# 2-18_11_03_04_08_3.net
KiCad netlist of a schematic drawn in Altium Designer
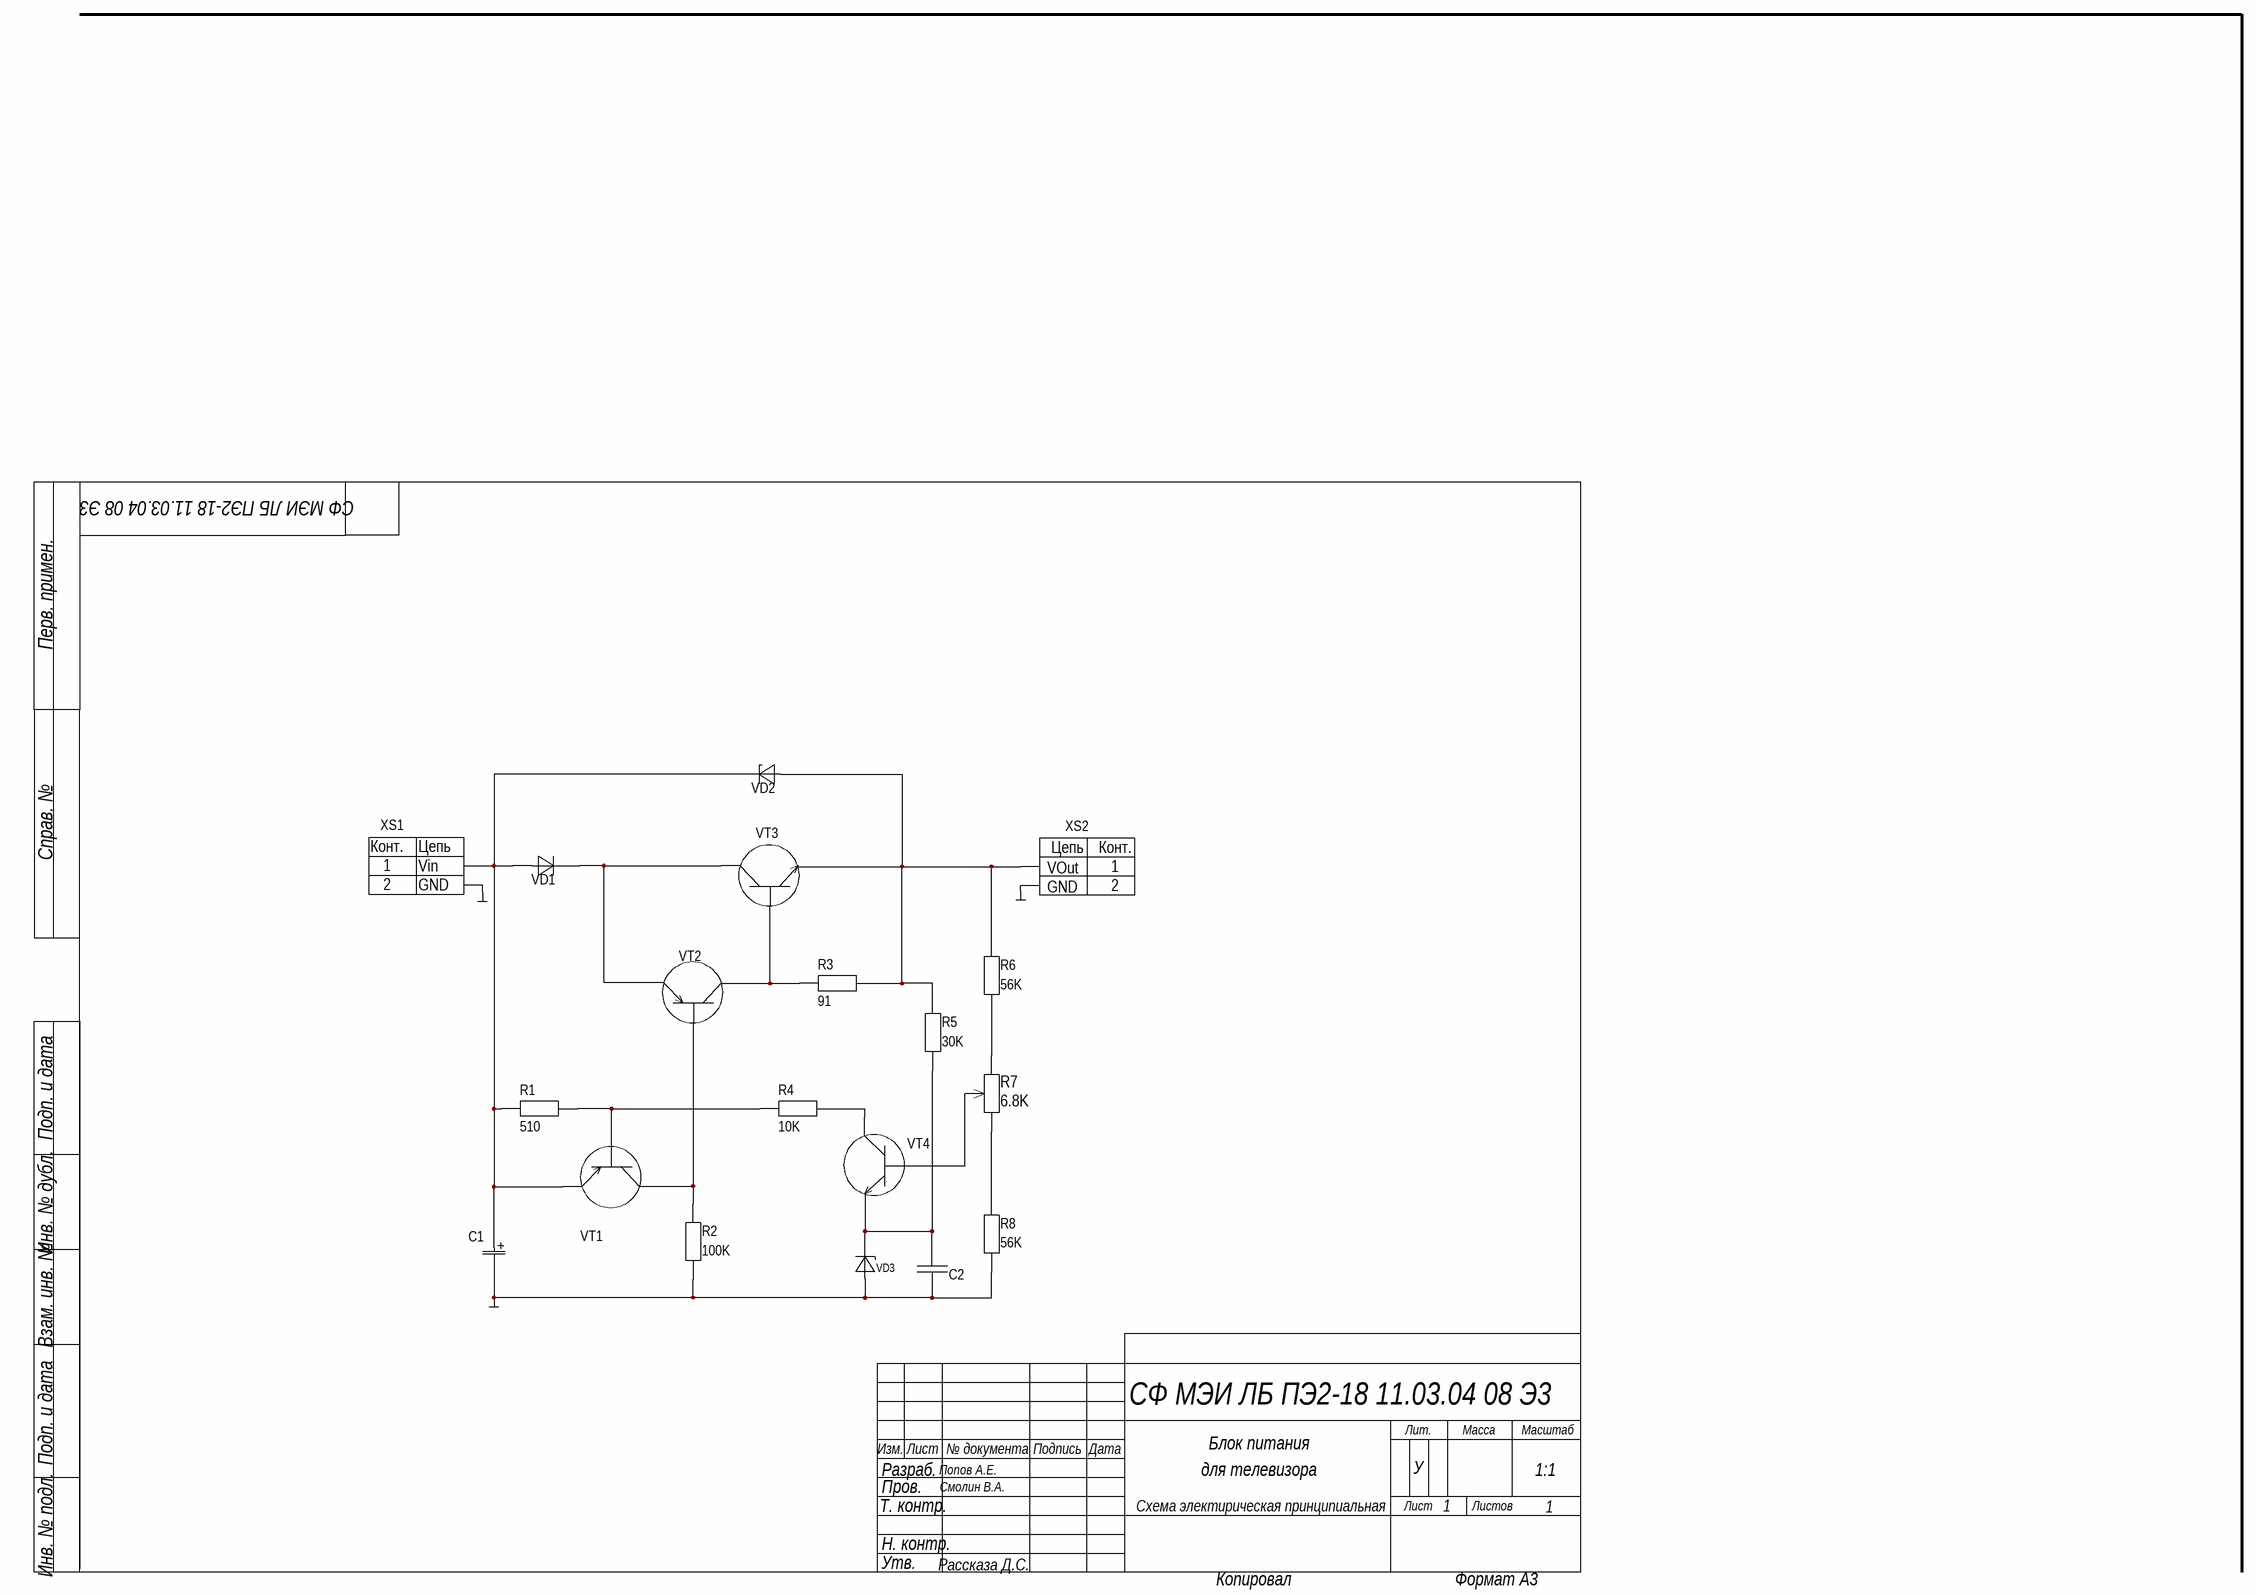
[diagram p0: СФ МЭИ ЛБ ПЭ2-18 11.03.04 08 Э3.SchDoc]

(export (version "E")
  (design (tool "Eeschema 10.0.6"))
  (components
    (comp (ref "C1")
      (value "Part Number: 35TZV330M10X10.5")
      (footprint "CAP_J-V_10X10P5")
      (description "No Description Available")
      (fields
        (field (name "MANUFACTURER_PART_NUMBER") "35TZV330M10X10.5")
        (field (name "COPYRIGHT") "Copyright (C) 2018 Accelerated Designs. All rights reserved")
      )
      (libsource (lib "SMD Elektrilits") (part "35TZV330M10X10.5"))
    )
    (comp (ref "C2")
      (value "0.068u")
      (footprint "0805")
      (description "К53-68\"R\"-25В-0.068 мкФ ±10%")
      (libsource (lib "УГО") (part "К53-68{dblquote}R{dblquote}-25В-0.068 мкФ ±10% 0805"))
    )
    (comp (ref "R1")
      (value "510")
      (footprint "0805")
      (description "0805-0.125 Вт -300 Ом±5%")
      (libsource (lib "УГО") (part "0.125Вт 0805 300 Ом, 5%, Чип резистор (SMD)"))
    )
    (comp (ref "R2")
      (value "100K")
      (footprint "0805")
      (description "0805-0.125 Вт -300 Ом±5%")
      (libsource (lib "УГО") (part "0.125Вт 0805 300 Ом, 5%, Чип резистор (SMD)"))
    )
    (comp (ref "R3")
      (value "91")
      (footprint "0805")
      (description "0805-0.125 Вт -300 Ом±5%")
      (libsource (lib "УГО") (part "0.125Вт 0805 300 Ом, 5%, Чип резистор (SMD)"))
    )
    (comp (ref "R4")
      (value "10K")
      (footprint "0805")
      (description "0805-0.125 Вт -300 Ом±5%")
      (libsource (lib "УГО") (part "0.125Вт 0805 300 Ом, 5%, Чип резистор (SMD)"))
    )
    (comp (ref "R5")
      (value "30K")
      (footprint "0805")
      (description "0805-0.125 Вт -300 Ом±5%")
      (libsource (lib "УГО") (part "0.125Вт 0805 300 Ом, 5%, Чип резистор (SMD)"))
    )
    (comp (ref "R6")
      (value "56K")
      (footprint "0805")
      (description "0805-0.125 Вт -300 Ом±5%")
      (libsource (lib "УГО") (part "0.125Вт 0805 300 Ом, 5%, Чип резистор (SMD)"))
    )
    (comp (ref "R7")
      (value "6.8K")
      (footprint "ST32")
      (description "0805-0.125 Вт -6.8 кОм±5%")
      (libsource (lib "УГО") (part "0.125Вт 0805 6.8 кОм, 5%, подстроечный чип резистор (SMD)"))
    )
    (comp (ref "R8")
      (value "56K")
      (footprint "0805")
      (description "0805-0.125 Вт -300 Ом±5%")
      (libsource (lib "УГО") (part "0.125Вт 0805 300 Ом, 5%, Чип резистор (SMD)"))
    )
    (comp (ref "VD1")
      (value "MMSZ5235B_1")
      (footprint "SOD-123")
      (description "MMSZ5235B")
      (libsource (lib "УГО") (part "MMSZ5235B_1"))
    )
    (comp (ref "VD2") (value "MMSZ5235B") (footprint "SOD-123") (libsource (lib "УГО") (part "MMSZ5235B")))
    (comp (ref "VD3") (value "MMSZ5235B") (footprint "SOD-123") (libsource (lib "УГО") (part "MMSZ5235B")))
    (comp (ref "VT1")
      (value "Биполярный транзистор n-p-n")
      (footprint "SOT23")
      (description "IRFML8244TRPBF")
      (libsource (lib "УГО") (part "IRFML8244TRPBF_1"))
    )
    (comp (ref "VT2")
      (value "Биполярный транзистор n-p-n")
      (footprint "SOT23")
      (description "IRFML8244TRPBF")
      (libsource (lib "УГО") (part "IRFML8244TRPBF_1"))
    )
    (comp (ref "VT3")
      (value "Биполярный транзистор n-p-n")
      (footprint "SOT23")
      (description "IRFML8244TRPBF")
      (libsource (lib "УГО") (part "IRFML8244TRPBF"))
    )
    (comp (ref "VT4")
      (value "Биполярный транзистор n-p-n")
      (footprint "SOT23")
      (description "IRFML8244TRPBF")
      (libsource (lib "УГО") (part "IRFML8244TRPBF"))
    )
    (comp (ref "XS1")
      (value "DG126-5.0-0.2P")
      (footprint "DG126-5.0-02P")
      (libsource (lib "УГО") (part "DG126-5.0-0.2P"))
    )
    (comp (ref "XS2")
      (value "DG126-5.0-0.2P")
      (footprint "DG126-5.0-02P")
      (libsource (lib "УГО") (part "DG126-5.0-0.2P"))
    )
  )
  (nets
    (net (code "1") (name "<NO NET>") (class "Default")
      (node (ref "C1") (pin "2") (pinfunction "2_2") (pintype "power_in"))
      (node (ref "C2") (pin "1") (pinfunction "1_1") (pintype "passive"))
      (node (ref "R2") (pin "1") (pinfunction "1_1") (pintype "passive"))
      (node (ref "R8") (pin "1") (pinfunction "1_1") (pintype "passive"))
      (node (ref "VD3") (pin "1") (pinfunction "In_1") (pintype "passive"))
      (node (ref "XS1") (pin "2") (pinfunction "Pin2_2") (pintype "passive"))
      (node (ref "XS2") (pin "2") (pinfunction "Pin2_2") (pintype "passive"))
    )
    (net (code "2") (name "Net-(R6-Pad1)") (class "Default")
      (node (ref "R6") (pin "1") (pinfunction "1_1") (pintype "passive"))
      (node (ref "R7") (pin "2") (pinfunction "2_2") (pintype "passive"))
    )
    (net (code "3") (name "Net-(R7-Pad1)") (class "Default")
      (node (ref "R7") (pin "1") (pinfunction "1_1") (pintype "passive"))
      (node (ref "R8") (pin "2") (pinfunction "2_2") (pintype "passive"))
    )
    (net (code "4") (name "Net-(VD1-In)") (class "Default")
      (node (ref "C1") (pin "1") (pinfunction "1_1") (pintype "power_in"))
      (node (ref "R1") (pin "1") (pinfunction "1_1") (pintype "passive"))
      (node (ref "VD1") (pin "1") (pinfunction "In_1") (pintype "passive"))
      (node (ref "VD2") (pin "2") (pinfunction "Out_2") (pintype "passive"))
      (node (ref "VT1") (pin "2") (pinfunction "E_2") (pintype "passive"))
      (node (ref "XS1") (pin "1") (pinfunction "Pin1_1") (pintype "passive"))
    )
    (net (code "5") (name "Net-(VD1-Out)") (class "Default")
      (node (ref "VD1") (pin "2") (pinfunction "Out_2") (pintype "passive"))
      (node (ref "VT2") (pin "2") (pinfunction "E_2") (pintype "passive"))
      (node (ref "VT3") (pin "2") (pinfunction "E_2") (pintype "passive"))
    )
    (net (code "6") (name "Net-(VD2-In)") (class "Default")
      (node (ref "R3") (pin "2") (pinfunction "2_2") (pintype "passive"))
      (node (ref "R5") (pin "2") (pinfunction "2_2") (pintype "passive"))
      (node (ref "R6") (pin "2") (pinfunction "2_2") (pintype "passive"))
      (node (ref "VD2") (pin "1") (pinfunction "In_1") (pintype "passive"))
      (node (ref "VT3") (pin "3") (pinfunction "K_3") (pintype "passive"))
      (node (ref "XS2") (pin "1") (pinfunction "Pin1_1") (pintype "passive"))
    )
    (net (code "7") (name "Net-(VD3-Out)") (class "Default")
      (node (ref "C2") (pin "2") (pinfunction "2_2") (pintype "passive"))
      (node (ref "R5") (pin "1") (pinfunction "1_1") (pintype "passive"))
      (node (ref "VD3") (pin "2") (pinfunction "Out_2") (pintype "passive"))
      (node (ref "VT4") (pin "3") (pinfunction "K_3") (pintype "passive"))
    )
    (net (code "8") (name "Net-(VT1-B)") (class "Default")
      (node (ref "R1") (pin "2") (pinfunction "2_2") (pintype "passive"))
      (node (ref "R4") (pin "1") (pinfunction "1_1") (pintype "passive"))
      (node (ref "VT1") (pin "1") (pinfunction "B_1") (pintype "passive"))
    )
    (net (code "9") (name "Net-(VT1-K)") (class "Default")
      (node (ref "R2") (pin "2") (pinfunction "2_2") (pintype "passive"))
      (node (ref "VT1") (pin "3") (pinfunction "K_3") (pintype "passive"))
      (node (ref "VT2") (pin "1") (pinfunction "B_1") (pintype "passive"))
    )
    (net (code "10") (name "Net-(VT2-K)") (class "Default")
      (node (ref "R3") (pin "1") (pinfunction "1_1") (pintype "passive"))
      (node (ref "VT2") (pin "3") (pinfunction "K_3") (pintype "passive"))
      (node (ref "VT3") (pin "1") (pinfunction "B_1") (pintype "passive"))
    )
    (net (code "11") (name "Net-(VT4-B)") (class "Default")
      (node (ref "R7") (pin "3") (pinfunction "3_3") (pintype "passive"))
      (node (ref "VT4") (pin "1") (pinfunction "B_1") (pintype "passive"))
    )
    (net (code "12") (name "Net-(VT4-E)") (class "Default")
      (node (ref "R4") (pin "2") (pinfunction "2_2") (pintype "passive"))
      (node (ref "VT4") (pin "2") (pinfunction "E_2") (pintype "passive"))
    )
  )
)
